# P15_ETH3_USB__USB_2_0_HUB.net
KiCad netlist of a schematic drawn in Altium Designer
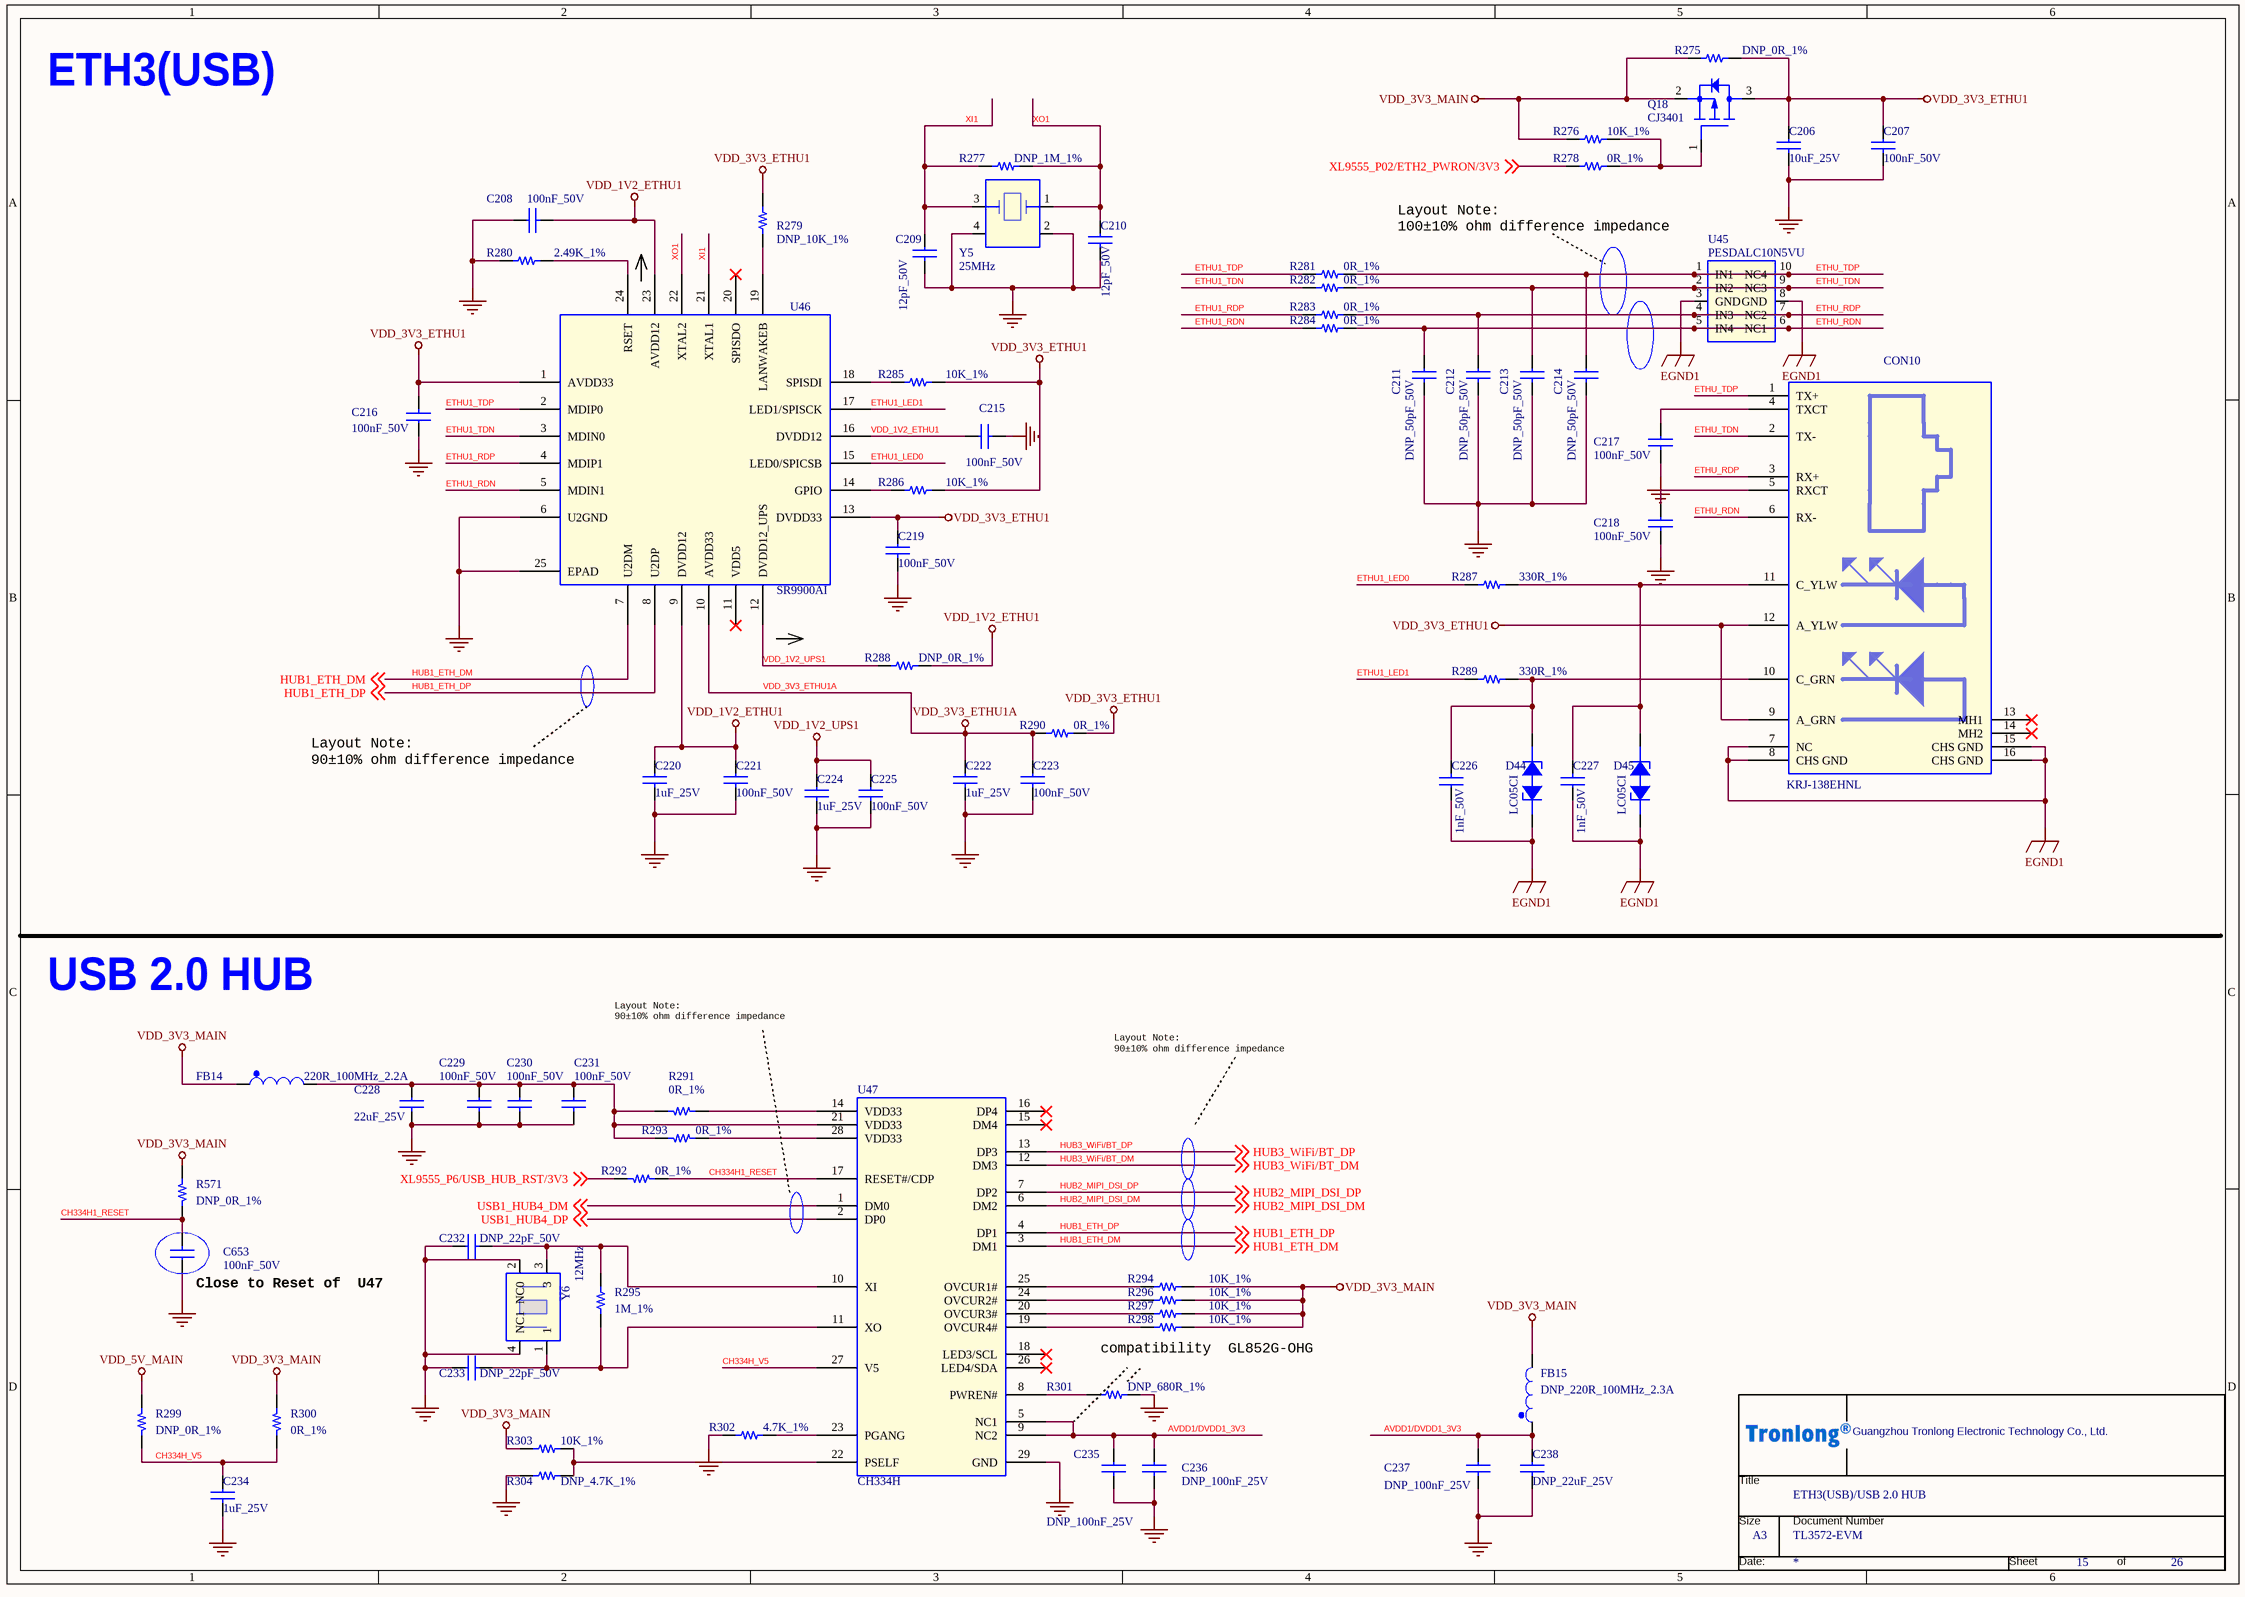
[diagram p0: P15_ETH3(USB)_USB 2.0 HUB.SchDoc]

(export (version "E")
  (design (tool "Eeschema 10.0.6"))
  (components
    (comp (ref "*")
      (value "Tronlong_TITTLE_20211115")
      (fields
        (field (name "DOC") "TL3572-EVM")
        (field (name "TITLE") "ETH3(USB)/USB 2.0 HUB")
        (field (name "ORGNAME") "Guangzhou Tronlong Electronic Technology Co., Ltd.")
        (field (name "PAGE SIZE") "A3")
        (field (name "PAGE NUMBER") "15")
        (field (name "PAGE COUNT") "26")
      )
      (libsource (lib "*") (part "Tronlong_TITTLE_20211115"))
    )
    (comp (ref "C206")
      (value "10uF_25V")
      (footprint "C0603")
      (description "贴片陶瓷电容,10uF,20%,25V,X5R")
      (fields
        (field (name "MANUFACTURER") "广东风华高新科技股份有限公司（FH）")
        (field (name "MANUFACTURER PARTNUMBER") "0603X106M250NT")
      )
      (libsource (lib "*") (part "CAP NP_Dup2"))
    )
    (comp (ref "C207")
      (value "100nF_50V")
      (footprint "C0402")
      (description "贴片陶瓷电容,100nF,10%,50V,X7R")
      (fields
        (field (name "MANUFACTURER") "广东风华高新科技股份有限公司（FH）")
        (field (name "MANUFACTURER PARTNUMBER") "0402B104K500NT")
      )
      (libsource (lib "*") (part "CAP NP_Dup2"))
    )
    (comp (ref "C208")
      (value "100nF_50V")
      (footprint "C0402")
      (description "贴片陶瓷电容,100nF,10%,50V,X7R")
      (fields
        (field (name "MANUFACTURER") "广东风华高新科技股份有限公司（FH）")
        (field (name "MANUFACTURER PARTNUMBER") "0402B104K500NT")
      )
      (libsource (lib "*") (part "CAP NP_Dup2"))
    )
    (comp (ref "C209")
      (value "12pF_50V")
      (footprint "C0402")
      (description "贴片陶瓷电容,12pF,5%,50V,COG")
      (fields
        (field (name "MANUFACTURER") "广东风华高新科技股份有限公司（FH）")
        (field (name "MANUFACTURER PARTNUMBER") "0402CG120J500NT")
      )
      (libsource (lib "*") (part "CAP NP_Dup2"))
    )
    (comp (ref "C210")
      (value "12pF_50V")
      (footprint "C0402")
      (description "贴片陶瓷电容,12pF,5%,50V,COG")
      (fields
        (field (name "MANUFACTURER PARTNUMBER") "0402CG120J500NT")
        (field (name "MANUFACTURER") "广东风华高新科技股份有限公司（FH）")
      )
      (libsource (lib "*") (part "CAP NP_Dup2"))
    )
    (comp (ref "C211")
      (value "DNP_50pF_50V")
      (footprint "C0402")
      (description "贴片陶瓷电容,100nF,10%,50V,X7R")
      (fields
        (field (name "MANUFACTURER") "广东风华高新科技股份有限公司（FH）")
        (field (name "MANUFACTURER PARTNUMBER") "0402B104K500NT")
      )
      (libsource (lib "*") (part "CAP NP_Dup2"))
    )
    (comp (ref "C212")
      (value "DNP_50pF_50V")
      (footprint "C0402")
      (description "贴片陶瓷电容,100nF,10%,50V,X7R")
      (fields
        (field (name "MANUFACTURER") "广东风华高新科技股份有限公司（FH）")
        (field (name "MANUFACTURER PARTNUMBER") "0402B104K500NT")
      )
      (libsource (lib "*") (part "CAP NP_Dup2"))
    )
    (comp (ref "C213")
      (value "DNP_50pF_50V")
      (footprint "C0402")
      (description "贴片陶瓷电容,100nF,10%,50V,X7R")
      (fields
        (field (name "MANUFACTURER") "广东风华高新科技股份有限公司（FH）")
        (field (name "MANUFACTURER PARTNUMBER") "0402B104K500NT")
      )
      (libsource (lib "*") (part "CAP NP_Dup2"))
    )
    (comp (ref "C214")
      (value "DNP_50pF_50V")
      (footprint "C0402")
      (description "贴片陶瓷电容,100nF,10%,50V,X7R")
      (fields
        (field (name "MANUFACTURER") "广东风华高新科技股份有限公司（FH）")
        (field (name "MANUFACTURER PARTNUMBER") "0402B104K500NT")
      )
      (libsource (lib "*") (part "CAP NP_Dup2"))
    )
    (comp (ref "C215")
      (value "100nF_50V")
      (footprint "C0402")
      (description "贴片陶瓷电容,100nF,10%,50V,X7R")
      (fields
        (field (name "MANUFACTURER PARTNUMBER") "0402B104K500NT")
        (field (name "MANUFACTURER") "广东风华高新科技股份有限公司（FH）")
      )
      (libsource (lib "*") (part "CAP NP_Dup2"))
    )
    (comp (ref "C216")
      (value "100nF_50V")
      (footprint "C0402")
      (description "贴片陶瓷电容,100nF,10%,50V,X7R")
      (fields
        (field (name "MANUFACTURER") "广东风华高新科技股份有限公司（FH）")
        (field (name "MANUFACTURER PARTNUMBER") "0402B104K500NT")
      )
      (libsource (lib "*") (part "CAP NP_Dup2"))
    )
    (comp (ref "C217")
      (value "100nF_50V")
      (footprint "C0402")
      (description "贴片陶瓷电容,100nF,10%,50V,X7R")
      (fields
        (field (name "MANUFACTURER") "广东风华高新科技股份有限公司（FH）")
        (field (name "MANUFACTURER PARTNUMBER") "0402B104K500NT")
      )
      (libsource (lib "*") (part "CAP NP_Dup2"))
    )
    (comp (ref "C218")
      (value "100nF_50V")
      (footprint "C0402")
      (description "贴片陶瓷电容,100nF,10%,50V,X7R")
      (fields
        (field (name "MANUFACTURER PARTNUMBER") "0402B104K500NT")
        (field (name "MANUFACTURER") "广东风华高新科技股份有限公司（FH）")
      )
      (libsource (lib "*") (part "CAP NP_Dup2"))
    )
    (comp (ref "C219")
      (value "100nF_50V")
      (footprint "C0402")
      (description "贴片陶瓷电容,100nF,10%,50V,X7R")
      (fields
        (field (name "MANUFACTURER") "广东风华高新科技股份有限公司（FH）")
        (field (name "MANUFACTURER PARTNUMBER") "0402B104K500NT")
      )
      (libsource (lib "*") (part "CAP NP_Dup2"))
    )
    (comp (ref "C220")
      (value "1uF_25V")
      (footprint "C0402")
      (description "贴片陶瓷电容,1uF,10%,25V,X5R")
      (fields
        (field (name "MANUFACTURER") "广东风华高新科技股份有限公司（FH）")
        (field (name "MANUFACTURER PARTNUMBER") "0402X105K250NT")
      )
      (libsource (lib "*") (part "CAP NP_Dup2"))
    )
    (comp (ref "C221")
      (value "100nF_50V")
      (footprint "C0402")
      (description "贴片陶瓷电容,100nF,10%,50V,X7R")
      (fields
        (field (name "MANUFACTURER PARTNUMBER") "0402B104K500NT")
        (field (name "MANUFACTURER") "广东风华高新科技股份有限公司（FH）")
      )
      (libsource (lib "*") (part "CAP NP_Dup2"))
    )
    (comp (ref "C222")
      (value "1uF_25V")
      (footprint "C0402")
      (description "贴片陶瓷电容,1uF,10%,25V,X5R")
      (fields
        (field (name "MANUFACTURER") "广东风华高新科技股份有限公司（FH）")
        (field (name "MANUFACTURER PARTNUMBER") "0402X105K250NT")
      )
      (libsource (lib "*") (part "CAP NP_Dup2"))
    )
    (comp (ref "C223")
      (value "100nF_50V")
      (footprint "C0402")
      (description "贴片陶瓷电容,100nF,10%,50V,X7R")
      (fields
        (field (name "MANUFACTURER") "广东风华高新科技股份有限公司（FH）")
        (field (name "MANUFACTURER PARTNUMBER") "0402B104K500NT")
      )
      (libsource (lib "*") (part "CAP NP_Dup2"))
    )
    (comp (ref "C224")
      (value "1uF_25V")
      (footprint "C0402")
      (description "贴片陶瓷电容,1uF,10%,25V,X5R")
      (fields
        (field (name "MANUFACTURER") "广东风华高新科技股份有限公司（FH）")
        (field (name "MANUFACTURER PARTNUMBER") "0402X105K250NT")
      )
      (libsource (lib "*") (part "CAP NP_Dup2"))
    )
    (comp (ref "C225")
      (value "100nF_50V")
      (footprint "C0402")
      (description "贴片陶瓷电容,100nF,10%,50V,X7R")
      (fields
        (field (name "MANUFACTURER PARTNUMBER") "0402B104K500NT")
        (field (name "MANUFACTURER") "广东风华高新科技股份有限公司（FH）")
      )
      (libsource (lib "*") (part "CAP NP_Dup2"))
    )
    (comp (ref "C226")
      (value "1nF_50V")
      (footprint "C0402")
      (description "贴片陶瓷电容,1nF,10%,50V,X7R")
      (fields
        (field (name "TOLERANCE") "±10%")
        (field (name "MANUFACTURER") "广东风华高新科技股份有限公司（FH）")
        (field (name "CREATED BY") "JJJ")
      )
      (libsource (lib "*") (part "CAP NP_1"))
    )
    (comp (ref "C227")
      (value "1nF_50V")
      (footprint "C0402")
      (description "贴片陶瓷电容,1nF,10%,50V,X7R")
      (fields
        (field (name "MANUFACTURER PARTNUMBER") "0402B102K500NT")
        (field (name "MANUFACTURER") "广东风华高新科技股份有限公司（FH）")
        (field (name "CREATED BY") "JJJ")
      )
      (libsource (lib "*") (part "CAP NP_1"))
    )
    (comp (ref "C228")
      (value "22uF_25V")
      (footprint "C0805")
      (description "贴片陶瓷电容,22uF,20%,25V,X5R")
      (fields
        (field (name "MANUFACTURER PARTNUMBER") "0805X226M250NT")
        (field (name "MANUFACTURER") "广东风华高新科技股份有限公司（FH）")
      )
      (libsource (lib "*") (part "CAP NP_Dup2"))
    )
    (comp (ref "C229")
      (value "100nF_50V")
      (footprint "C0402")
      (description "贴片陶瓷电容,100nF,10%,50V,X7R")
      (fields
        (field (name "MANUFACTURER PARTNUMBER") "0402B104K500NT")
        (field (name "MANUFACTURER") "广东风华高新科技股份有限公司（FH）")
      )
      (libsource (lib "*") (part "CAP NP_Dup2"))
    )
    (comp (ref "C230")
      (value "100nF_50V")
      (footprint "C0402")
      (description "贴片陶瓷电容,100nF,10%,50V,X7R")
      (fields
        (field (name "MANUFACTURER PARTNUMBER") "0402B104K500NT")
        (field (name "MANUFACTURER") "广东风华高新科技股份有限公司（FH）")
      )
      (libsource (lib "*") (part "CAP NP_Dup2"))
    )
    (comp (ref "C231")
      (value "100nF_50V")
      (footprint "C0402")
      (description "贴片陶瓷电容,100nF,10%,50V,X7R")
      (fields
        (field (name "MANUFACTURER PARTNUMBER") "0402B104K500NT")
        (field (name "MANUFACTURER") "广东风华高新科技股份有限公司（FH）")
      )
      (libsource (lib "*") (part "CAP NP_Dup2"))
    )
    (comp (ref "C232")
      (value "DNP_22pF_50V")
      (footprint "C0603")
      (description "贴片陶瓷电容,22pF,5%,50V,COG")
      (fields
        (field (name "MANUFACTURER PARTNUMBER") "0603CG220J500NT")
        (field (name "MANUFACTURER") "广东风华高新科技股份有限公司（FH）")
      )
      (libsource (lib "*") (part "CAP NP_Dup2"))
    )
    (comp (ref "C233")
      (value "DNP_22pF_50V")
      (footprint "C0603")
      (description "贴片陶瓷电容,22pF,5%,50V,COG")
      (fields
        (field (name "MANUFACTURER") "广东风华高新科技股份有限公司（FH）")
        (field (name "MANUFACTURER PARTNUMBER") "0603CG220J500NT")
      )
      (libsource (lib "*") (part "CAP NP_Dup2"))
    )
    (comp (ref "C234")
      (value "1uF_25V")
      (footprint "C0402")
      (description "贴片陶瓷电容,1uF,10%,25V,X5R")
      (fields
        (field (name "MANUFACTURER") "广东风华高新科技股份有限公司（FH）")
        (field (name "MANUFACTURER PARTNUMBER") "0402X105K250NT")
      )
      (libsource (lib "*") (part "CAP NP_Dup2"))
    )
    (comp (ref "C235")
      (value "DNP_100nF_25V")
      (footprint "C0402")
      (description "贴片陶瓷电容,100nF,10%,25V,X7R")
      (fields
        (field (name "MANUFACTURER PARTNUMBER") "0402B104K250NT")
        (field (name "MANUFACTURER") "广东风华高新科技股份有限公司（FH）")
      )
      (libsource (lib "*") (part "CAP NP_Dup2"))
    )
    (comp (ref "C236")
      (value "DNP_100nF_25V")
      (footprint "C0402")
      (description "贴片陶瓷电容,100nF,10%,25V,X7R")
      (fields
        (field (name "MANUFACTURER PARTNUMBER") "0402B104K250NT")
        (field (name "MANUFACTURER") "广东风华高新科技股份有限公司（FH）")
      )
      (libsource (lib "*") (part "CAP NP_Dup2"))
    )
    (comp (ref "C237")
      (value "DNP_100nF_25V")
      (footprint "C0402")
      (description "贴片陶瓷电容,100nF,10%,25V,X7R")
      (fields
        (field (name "MANUFACTURER") "广东风华高新科技股份有限公司（FH）")
        (field (name "MANUFACTURER PARTNUMBER") "0402B104K250NT")
      )
      (libsource (lib "*") (part "CAP NP_Dup2"))
    )
    (comp (ref "C238")
      (value "DNP_22uF_25V")
      (footprint "C0805")
      (description "CL21A226MAQNNNE，CL21A226MAYNNNE")
      (fields
        (field (name "MANUFACTURER PARTNUMBER") "22uF,20%,C0805,25V,（X7R,X5R,COG,NPO或X7S）")
        (field (name "MANUFACTURER") "广州创龙")
      )
      (libsource (lib "*") (part "CAP NP_Dup2"))
    )
    (comp (ref "C653")
      (value "100nF_50V")
      (footprint "C0402")
      (description "贴片陶瓷电容,100nF,10%,50V,X7R")
      (fields
        (field (name "MANUFACTURER") "广东风华高新科技股份有限公司（FH）")
        (field (name "MANUFACTURER PARTNUMBER") "0402B104K500NT")
      )
      (libsource (lib "*") (part "CAP NP_Dup2"))
    )
    (comp (ref "CON10")
      (value "KRJ-138EHNL")
      (footprint "CON_YDS_13F-64GYD2PLXNL")
      (description "RJ45连接器,12P,2.54mm间距,单层母座,90度,插件")
      (fields (field (name "MANUFACTURER") "东莞市科优达电子科技有限公司（DGKYD）"))
      (libsource (lib "*") (part "ETHERNET CONNECTER"))
    )
    (comp (ref "D44")
      (value "LC05CI")
      (footprint "SOD323")
      (description "TVS二极管,VRWM=5V,VBR=6V,一组,双向,30KV,30KV")
      (fields
        (field (name "MANUFACTURER") "上海雷卯电子科技有限公司（Leiditech）")
        (field (name "MANUFACTURER PART NUMBER") "PESD3V3L1BA")
      )
      (libsource (lib "*") (part "DIODE BREAKDOWN_2"))
    )
    (comp (ref "D45")
      (value "LC05CI")
      (footprint "SOD323")
      (description "TVS二极管,VRWM=5V,VBR=6V,一组,双向,30KV,30KV")
      (fields
        (field (name "MANUFACTURER") "上海雷卯电子科技有限公司（Leiditech）")
        (field (name "MANUFACTURER PART NUMBER") "PESD3V3L1BA")
      )
      (libsource (lib "*") (part "DIODE BREAKDOWN_2"))
    )
    (comp (ref "FB14")
      (value "220R_100MHz_2.2A")
      (footprint "L0603")
      (description "磁珠,50mΩ,2.2A,220R@100MHz")
      (fields
        (field (name "MANUFACTURER PARTNUMBER") "UPZ1608U221-2R2TF")
        (field (name "MANUFACTURER") "深圳顺络电子股份有限公司（Sunlord）")
      )
      (libsource (lib "*") (part "FERRITE BEAD"))
    )
    (comp (ref "FB15")
      (value "DNP_220R_100MHz_2.3A")
      (footprint "L0603")
      (description "磁珠,50mΩ,2.3A,220R@100MHz")
      (fields
        (field (name "MANUFACTURER PARTNUMBER") "UPZ1608U221-2R3TF")
        (field (name "MANUFACTURER") "深圳顺络电子股份有限公司（Sunlord）")
      )
      (libsource (lib "*") (part "FERRITE BEAD"))
    )
    (comp (ref "Q18")
      (value "CJ3401")
      (footprint "SOT23-3")
      (description "MOSFET,P沟道,VDSS=-30V,VGSS=±12V,ID=-4.2A,PD=0.35W,VGS(th)=-1.3V")
      (fields (field (name "MANUFACTURER") "江苏长晶科技股份有限公司（JSCJ）"))
      (libsource (lib "*") (part "MOSFET P SOT"))
    )
    (comp (ref "R275")
      (value "DNP_0R_1%")
      (footprint "R0603")
      (description "贴片电阻,0R,±1%,1/10W")
      (fields
        (field (name "MANUFACTURER PARTNUMBER") "RS-03000FT")
        (field (name "MANUFACTURER") "广东风华高新科技股份有限公司（FH）")
      )
      (libsource (lib "*") (part "Resistor_Dup3"))
    )
    (comp (ref "R276")
      (value "10K_1%")
      (footprint "R0402")
      (description "贴片电阻,10K,±1%,1/16W")
      (fields
        (field (name "MANUFACTURER") "广东风华高新科技股份有限公司（FH）")
        (field (name "MANUFACTURER PARTNUMBER") "RC-02K1002FT")
      )
      (libsource (lib "*") (part "Resistor_Dup3"))
    )
    (comp (ref "R277")
      (value "DNP_1M_1%")
      (footprint "R0603")
      (description "0603WAF1004T5E,RC0603FR-071ML")
      (fields
        (field (name "MANUFACTURER") "广州创龙")
        (field (name "MANUFACTURER PARTNUMBER") "1M,±1%,R0603,≥1/10W")
      )
      (libsource (lib "*") (part "Resistor_Dup3"))
    )
    (comp (ref "R278")
      (value "0R_1%")
      (footprint "R0402")
      (description "贴片电阻,0R,±1%,1/16W")
      (fields
        (field (name "MANUFACTURER PARTNUMBER") "RC-02000FT")
        (field (name "MANUFACTURER") "广东风华高新科技股份有限公司（FH）")
      )
      (libsource (lib "*") (part "Resistor_Dup3"))
    )
    (comp (ref "R279")
      (value "DNP_10K_1%")
      (footprint "R0402")
      (description "贴片电阻,10K,±1%,1/16W")
      (fields
        (field (name "MANUFACTURER PARTNUMBER") "RC-02K1002FT")
        (field (name "MANUFACTURER") "广东风华高新科技股份有限公司（FH）")
      )
      (libsource (lib "*") (part "Resistor_Dup3"))
    )
    (comp (ref "R280")
      (value "2.49K_1%")
      (footprint "R0603")
      (description "贴片电阻,2.49K,±1%,1/10W")
      (fields
        (field (name "MANUFACTURER PARTNUMBER") "RS-03K2491FT")
        (field (name "MANUFACTURER") "广东风华高新科技股份有限公司（FH）")
      )
      (libsource (lib "*") (part "Resistor_Dup3"))
    )
    (comp (ref "R281")
      (value "0R_1%")
      (footprint "R0402")
      (description "贴片电阻,0R,±1%,1/16W")
      (fields
        (field (name "MANUFACTURER") "广东风华高新科技股份有限公司（FH）")
        (field (name "MANUFACTURER PARTNUMBER") "RC-02000FT")
      )
      (libsource (lib "*") (part "Resistor_Dup3"))
    )
    (comp (ref "R282")
      (value "0R_1%")
      (footprint "R0402")
      (description "贴片电阻,0R,±1%,1/16W")
      (fields
        (field (name "MANUFACTURER") "广东风华高新科技股份有限公司（FH）")
        (field (name "MANUFACTURER PARTNUMBER") "RC-02000FT")
      )
      (libsource (lib "*") (part "Resistor_Dup3"))
    )
    (comp (ref "R283")
      (value "0R_1%")
      (footprint "R0402")
      (description "贴片电阻,0R,±1%,1/16W")
      (fields
        (field (name "MANUFACTURER") "广东风华高新科技股份有限公司（FH）")
        (field (name "MANUFACTURER PARTNUMBER") "RC-02000FT")
      )
      (libsource (lib "*") (part "Resistor_Dup3"))
    )
    (comp (ref "R284")
      (value "0R_1%")
      (footprint "R0402")
      (description "贴片电阻,0R,±1%,1/16W")
      (fields
        (field (name "MANUFACTURER") "广东风华高新科技股份有限公司（FH）")
        (field (name "MANUFACTURER PARTNUMBER") "RC-02000FT")
      )
      (libsource (lib "*") (part "Resistor_Dup3"))
    )
    (comp (ref "R285")
      (value "10K_1%")
      (footprint "R0402")
      (description "贴片电阻,10K,±1%,1/16W")
      (fields
        (field (name "MANUFACTURER") "广东风华高新科技股份有限公司（FH）")
        (field (name "MANUFACTURER PARTNUMBER") "RC-02K1002FT")
      )
      (libsource (lib "*") (part "Resistor_Dup3"))
    )
    (comp (ref "R286")
      (value "10K_1%")
      (footprint "R0402")
      (description "贴片电阻,10K,±1%,1/16W")
      (fields
        (field (name "MANUFACTURER PARTNUMBER") "RC-02K1002FT")
        (field (name "MANUFACTURER") "广东风华高新科技股份有限公司（FH）")
      )
      (libsource (lib "*") (part "Resistor_Dup3"))
    )
    (comp (ref "R287")
      (value "330R_1%")
      (footprint "R0402")
      (description "RC0402FR-07330RL,0402WGF3300TCE")
      (fields
        (field (name "MANUFACTURER PARTNUMBER") "330R,±1%,R0402,≥1/16W")
        (field (name "MANUFACTURER") "广州创龙")
      )
      (libsource (lib "*") (part "Resistor_Dup3"))
    )
    (comp (ref "R288")
      (value "DNP_0R_1%")
      (footprint "R0603")
      (description "贴片电阻,0R,±1%,1/10W")
      (fields
        (field (name "MANUFACTURER PARTNUMBER") "RS-03000FT")
        (field (name "MANUFACTURER") "广东风华高新科技股份有限公司（FH）")
      )
      (libsource (lib "*") (part "Resistor_Dup3"))
    )
    (comp (ref "R289")
      (value "330R_1%")
      (footprint "R0402")
      (description "RC0402FR-07330RL,0402WGF3300TCE")
      (fields
        (field (name "MANUFACTURER") "广州创龙")
        (field (name "MANUFACTURER PARTNUMBER") "330R,±1%,R0402,≥1/16W")
      )
      (libsource (lib "*") (part "Resistor_Dup3"))
    )
    (comp (ref "R290")
      (value "0R_1%")
      (footprint "R0603")
      (description "贴片电阻,0R,±1%,1/10W")
      (fields
        (field (name "MANUFACTURER") "广东风华高新科技股份有限公司（FH）")
        (field (name "MANUFACTURER PARTNUMBER") "RS-03000FT")
      )
      (libsource (lib "*") (part "Resistor_Dup3"))
    )
    (comp (ref "R291")
      (value "0R_1%")
      (footprint "R0402")
      (description "贴片电阻,0R,±1%,1/16W")
      (fields
        (field (name "MANUFACTURER") "广东风华高新科技股份有限公司（FH）")
        (field (name "MANUFACTURER PARTNUMBER") "RC-02000FT")
      )
      (libsource (lib "*") (part "Resistor_Dup3"))
    )
    (comp (ref "R292")
      (value "0R_1%")
      (footprint "R0402")
      (description "贴片电阻,0R,±1%,1/16W")
      (fields
        (field (name "MANUFACTURER") "广东风华高新科技股份有限公司（FH）")
        (field (name "MANUFACTURER PARTNUMBER") "RC-02000FT")
      )
      (libsource (lib "*") (part "Resistor_Dup3"))
    )
    (comp (ref "R293")
      (value "0R_1%")
      (footprint "R0402")
      (description "贴片电阻,0R,±1%,1/16W")
      (fields
        (field (name "MANUFACTURER") "广东风华高新科技股份有限公司（FH）")
        (field (name "MANUFACTURER PARTNUMBER") "RC-02000FT")
      )
      (libsource (lib "*") (part "Resistor_Dup3"))
    )
    (comp (ref "R294")
      (value "10K_1%")
      (footprint "R0402")
      (description "贴片电阻,10K,±1%,1/16W")
      (fields
        (field (name "MANUFACTURER") "广东风华高新科技股份有限公司（FH）")
        (field (name "MANUFACTURER PARTNUMBER") "RC-02K1002FT")
      )
      (libsource (lib "*") (part "Resistor_Dup3"))
    )
    (comp (ref "R295")
      (value "1M_1%")
      (footprint "R0402")
      (description "RC0402FR-071ML,0402WGF1004TCE")
      (fields
        (field (name "MANUFACTURER PARTNUMBER") "1M,±1%,R0402,≥1/16W")
        (field (name "MANUFACTURER") "广州创龙")
      )
      (libsource (lib "*") (part "Resistor_Dup3"))
    )
    (comp (ref "R296")
      (value "10K_1%")
      (footprint "R0402")
      (description "贴片电阻,10K,±1%,1/16W")
      (fields
        (field (name "MANUFACTURER") "广东风华高新科技股份有限公司（FH）")
        (field (name "MANUFACTURER PARTNUMBER") "RC-02K1002FT")
      )
      (libsource (lib "*") (part "Resistor_Dup3"))
    )
    (comp (ref "R297")
      (value "10K_1%")
      (footprint "R0402")
      (description "贴片电阻,10K,±1%,1/16W")
      (fields
        (field (name "MANUFACTURER PARTNUMBER") "RC-02K1002FT")
        (field (name "MANUFACTURER") "广东风华高新科技股份有限公司（FH）")
      )
      (libsource (lib "*") (part "Resistor_Dup3"))
    )
    (comp (ref "R298")
      (value "10K_1%")
      (footprint "R0402")
      (description "贴片电阻,10K,±1%,1/16W")
      (fields
        (field (name "MANUFACTURER") "广东风华高新科技股份有限公司（FH）")
        (field (name "MANUFACTURER PARTNUMBER") "RC-02K1002FT")
      )
      (libsource (lib "*") (part "Resistor_Dup3"))
    )
    (comp (ref "R299")
      (value "DNP_0R_1%")
      (footprint "R0402")
      (description "贴片电阻,0R,±1%,1/16W")
      (fields
        (field (name "MANUFACTURER") "广东风华高新科技股份有限公司（FH）")
        (field (name "MANUFACTURER PARTNUMBER") "RC-02000FT")
      )
      (libsource (lib "*") (part "Resistor_Dup3"))
    )
    (comp (ref "R300")
      (value "0R_1%")
      (footprint "R0603")
      (description "贴片电阻,0R,±1%,1/10W")
      (fields
        (field (name "MANUFACTURER PARTNUMBER") "RS-03000FT")
        (field (name "MANUFACTURER") "广东风华高新科技股份有限公司（FH）")
      )
      (libsource (lib "*") (part "Resistor_Dup3"))
    )
    (comp (ref "R301")
      (value "DNP_680R_1%")
      (footprint "R0603")
      (description "贴片电阻,680R,±1%,1/10W")
      (fields
        (field (name "MANUFACTURER") "广东风华高新科技股份有限公司（FH）")
        (field (name "MANUFACTURER PARTNUMBER") "RS-03K6800FT")
      )
      (libsource (lib "*") (part "Resistor_Dup3"))
    )
    (comp (ref "R302")
      (value "4.7K_1%")
      (footprint "R0402")
      (description "贴片电阻,4.7K,±1%,1/16W")
      (fields
        (field (name "MANUFACTURER PARTNUMBER") "RC-02K4701FT")
        (field (name "MANUFACTURER") "广东风华高新科技股份有限公司（FH）")
      )
      (libsource (lib "*") (part "Resistor_Dup3"))
    )
    (comp (ref "R303")
      (value "10K_1%")
      (footprint "R0402")
      (description "贴片电阻,10K,±1%,1/16W")
      (fields
        (field (name "MANUFACTURER") "广东风华高新科技股份有限公司（FH）")
        (field (name "MANUFACTURER PARTNUMBER") "RC-02K1002FT")
      )
      (libsource (lib "*") (part "Resistor_Dup3"))
    )
    (comp (ref "R304")
      (value "DNP_4.7K_1%")
      (footprint "R0402")
      (description "RC0402FR-074K7L,0402WGF4701TCE")
      (fields
        (field (name "MANUFACTURER") "广州创龙")
        (field (name "MANUFACTURER PARTNUMBER") "4.7K,±1%,R0402,≥1/16W")
      )
      (libsource (lib "*") (part "Resistor_Dup3"))
    )
    (comp (ref "R571")
      (value "DNP_0R_1%")
      (footprint "R0402")
      (description "贴片电阻,0R,±1%,1/16W")
      (fields
        (field (name "MANUFACTURER PARTNUMBER") "RC-02000FT")
        (field (name "MANUFACTURER") "广东风华高新科技股份有限公司（FH）")
      )
      (libsource (lib "*") (part "Resistor_Dup3"))
    )
    (comp (ref "U45")
      (value "PESDALC10N5VU")
      (footprint "DFN-10-2510")
      (description "ESD二极管,VRWM=5V,VBR=6V,四组,单向,15KV,30KV")
      (fields (field (name "MANUFACTURER") "上海芯导电子科技股份有限公司（Prisemi）"))
      (libsource (lib "*") (part "SU099PGTR"))
    )
    (comp (ref "U46")
      (value "SR9900AI")
      (footprint "QFN24-4X4-0d5")
      (description "以太网控制器，USB")
      (fields (field (name "MANUFACTURER") "深圳市和芯润德科技有限公司（CoreChips）"))
      (libsource (lib "*") (part "SR9900_1"))
    )
    (comp (ref "U47")
      (value "CH334H")
      (footprint "QFN28_5x5")
      (description "USB HUB控制器")
      (fields (field (name "MANUFACTURER") "南京沁恒微电子股份有限公司（WCH）"))
      (libsource (lib "*") (part "GL852GT_1"))
    )
    (comp (ref "Y5")
      (value "25MHz")
      (footprint "SMD_3225")
      (description "四脚无源晶振,25MHz,±10ppm,12pF,30Ω,±30ppm")
      (fields
        (field (name "MANUFACTURER PARTNUMBER") "S3B25.000F1210F30")
        (field (name "MANUFACTURER") "深圳市星通时频电子有限公司（SCTF）")
      )
      (libsource (lib "*") (part "CRYSTAL SMD 4PIN"))
    )
    (comp (ref "Y6")
      (value "12MHz")
      (footprint "SMD_3225")
      (description "四脚无源晶振,12MHz,±10ppm,12pF,100Ω,±30ppm")
      (fields
        (field (name "MANUFACTURER PARTNUMBER") "S3B12.000F1210F30")
        (field (name "MANUFACTURER") "深圳市星通时频电子有限公司（SCTF）")
      )
      (libsource (lib "*") (part "CRYSTAL"))
    )
  )
  (nets
    (net (code "1") (name "/AVDD1{slash}DVDD1_3V3") (class "Default")
      (node (ref "C235") (pin "1") (pinfunction "1_1") (pintype "passive"))
      (node (ref "C236") (pin "1") (pinfunction "1_1") (pintype "passive"))
      (node (ref "C237") (pin "1") (pinfunction "1_1") (pintype "passive"))
      (node (ref "C238") (pin "1") (pinfunction "1_1") (pintype "passive"))
      (node (ref "FB15") (pin "1") (pinfunction "1_1") (pintype "passive"))
      (node (ref "U47") (pin "5") (pinfunction "NC1_5") (pintype "passive"))
      (node (ref "U47") (pin "9") (pinfunction "NC2_9") (pintype "passive"))
    )
    (net (code "2") (name "/CH334H1_RESET") (class "Default")
      (node (ref "C653") (pin "2") (pinfunction "2_2") (pintype "passive"))
      (node (ref "R292") (pin "1") (pinfunction "1_1") (pintype "passive"))
      (node (ref "R571") (pin "1") (pinfunction "1_1") (pintype "passive"))
      (node (ref "U47") (pin "17") (pinfunction "RESET#/CDP_17") (pintype "passive"))
    )
    (net (code "3") (name "/CH334H_V5") (class "Default")
      (node (ref "C234") (pin "1") (pinfunction "1_1") (pintype "passive"))
      (node (ref "R299") (pin "1") (pinfunction "1_1") (pintype "passive"))
      (node (ref "R300") (pin "1") (pinfunction "1_1") (pintype "passive"))
      (node (ref "U47") (pin "27") (pinfunction "V5_27") (pintype "passive"))
    )
    (net (code "4") (name "/ETHU1_LED0") (class "Default")
      (node (ref "R287") (pin "1") (pinfunction "1_1") (pintype "passive"))
      (node (ref "U46") (pin "15") (pinfunction "LED0/SPICSB_15") (pintype "passive"))
    )
    (net (code "5") (name "/ETHU1_LED1") (class "Default")
      (node (ref "R289") (pin "1") (pinfunction "1_1") (pintype "passive"))
      (node (ref "U46") (pin "17") (pinfunction "LED1/SPISCK_17") (pintype "passive"))
    )
    (net (code "6") (name "/ETHU1_RDN") (class "Default")
      (node (ref "R284") (pin "2") (pinfunction "2_2") (pintype "passive"))
      (node (ref "U46") (pin "5") (pinfunction "MDIN1_5") (pintype "passive"))
    )
    (net (code "7") (name "/ETHU1_RDP") (class "Default")
      (node (ref "R283") (pin "2") (pinfunction "2_2") (pintype "passive"))
      (node (ref "U46") (pin "4") (pinfunction "MDIP1_4") (pintype "passive"))
    )
    (net (code "8") (name "/ETHU1_TDN") (class "Default")
      (node (ref "R282") (pin "2") (pinfunction "2_2") (pintype "passive"))
      (node (ref "U46") (pin "3") (pinfunction "MDIN0_3") (pintype "passive"))
    )
    (net (code "9") (name "/ETHU1_TDP") (class "Default")
      (node (ref "R281") (pin "2") (pinfunction "2_2") (pintype "passive"))
      (node (ref "U46") (pin "2") (pinfunction "MDIP0_2") (pintype "passive"))
    )
    (net (code "10") (name "/ETHU_RDN") (class "Default")
      (node (ref "C211") (pin "1") (pinfunction "1_1") (pintype "passive"))
      (node (ref "CON10") (pin "6") (pinfunction "RX-_6") (pintype "passive"))
      (node (ref "R284") (pin "1") (pinfunction "1_1") (pintype "passive"))
      (node (ref "U45") (pin "5") (pinfunction "IN4_5") (pintype "passive"))
      (node (ref "U45") (pin "6") (pinfunction "NC1_6") (pintype "passive"))
    )
    (net (code "11") (name "/ETHU_RDP") (class "Default")
      (node (ref "C212") (pin "1") (pinfunction "1_1") (pintype "passive"))
      (node (ref "CON10") (pin "3") (pinfunction "RX+_3") (pintype "passive"))
      (node (ref "R283") (pin "1") (pinfunction "1_1") (pintype "passive"))
      (node (ref "U45") (pin "4") (pinfunction "IN3_4") (pintype "passive"))
      (node (ref "U45") (pin "7") (pinfunction "NC2_7") (pintype "passive"))
    )
    (net (code "12") (name "/ETHU_TDN") (class "Default")
      (node (ref "C213") (pin "1") (pinfunction "1_1") (pintype "passive"))
      (node (ref "CON10") (pin "2") (pinfunction "TX-_2") (pintype "passive"))
      (node (ref "R282") (pin "1") (pinfunction "1_1") (pintype "passive"))
      (node (ref "U45") (pin "2") (pinfunction "IN2_2") (pintype "passive"))
      (node (ref "U45") (pin "9") (pinfunction "NC3_9") (pintype "passive"))
    )
    (net (code "13") (name "/ETHU_TDP") (class "Default")
      (node (ref "C214") (pin "1") (pinfunction "1_1") (pintype "passive"))
      (node (ref "CON10") (pin "1") (pinfunction "TX+_1") (pintype "passive"))
      (node (ref "R281") (pin "1") (pinfunction "1_1") (pintype "passive"))
      (node (ref "U45") (pin "1") (pinfunction "IN1_1") (pintype "passive"))
      (node (ref "U45") (pin "10") (pinfunction "NC4_10") (pintype "passive"))
    )
    (net (code "14") (name "/XI1") (class "Default")
      (node (ref "C209") (pin "1") (pinfunction "1_1") (pintype "passive"))
      (node (ref "R277") (pin "2") (pinfunction "2_2") (pintype "passive"))
      (node (ref "U46") (pin "21") (pinfunction "XTAL1_21") (pintype "passive"))
      (node (ref "Y5") (pin "3") (pinfunction "3_3") (pintype "passive"))
    )
    (net (code "15") (name "/XO1") (class "Default")
      (node (ref "C210") (pin "1") (pinfunction "1_1") (pintype "passive"))
      (node (ref "R277") (pin "1") (pinfunction "1_1") (pintype "passive"))
      (node (ref "U46") (pin "22") (pinfunction "XTAL2_22") (pintype "passive"))
      (node (ref "Y5") (pin "1") (pinfunction "1_1") (pintype "passive"))
    )
    (net (code "16") (name "EGND1") (class "Default")
      (node (ref "C226") (pin "1") (pinfunction "1_1") (pintype "passive"))
      (node (ref "C227") (pin "1") (pinfunction "1_1") (pintype "passive"))
      (node (ref "CON10") (pin "15") (pinfunction "CHS_GND_15") (pintype "power_in"))
      (node (ref "CON10") (pin "16") (pinfunction "CHS_GND_16") (pintype "power_in"))
      (node (ref "CON10") (pin "7") (pinfunction "NC_7") (pintype "passive"))
      (node (ref "CON10") (pin "8") (pinfunction "CHS_GND_8") (pintype "power_in"))
      (node (ref "D44") (pin "1") (pinfunction "ANODE1_1") (pintype "passive"))
      (node (ref "D45") (pin "1") (pinfunction "ANODE1_1") (pintype "passive"))
      (node (ref "U45") (pin "3") (pinfunction "GND_3") (pintype "power_in"))
      (node (ref "U45") (pin "8") (pinfunction "GND_8") (pintype "power_in"))
    )
    (net (code "17") (name "GND") (class "Default")
      (node (ref "C206") (pin "2") (pinfunction "2_2") (pintype "passive"))
      (node (ref "C207") (pin "2") (pinfunction "2_2") (pintype "passive"))
      (node (ref "C208") (pin "1") (pinfunction "1_1") (pintype "passive"))
      (node (ref "C209") (pin "2") (pinfunction "2_2") (pintype "passive"))
      (node (ref "C210") (pin "2") (pinfunction "2_2") (pintype "passive"))
      (node (ref "C211") (pin "2") (pinfunction "2_2") (pintype "passive"))
      (node (ref "C212") (pin "2") (pinfunction "2_2") (pintype "passive"))
      (node (ref "C213") (pin "2") (pinfunction "2_2") (pintype "passive"))
      (node (ref "C214") (pin "2") (pinfunction "2_2") (pintype "passive"))
      (node (ref "C215") (pin "2") (pinfunction "2_2") (pintype "passive"))
      (node (ref "C216") (pin "1") (pinfunction "1_1") (pintype "passive"))
      (node (ref "C217") (pin "2") (pinfunction "2_2") (pintype "passive"))
      (node (ref "C218") (pin "2") (pinfunction "2_2") (pintype "passive"))
      (node (ref "C219") (pin "2") (pinfunction "2_2") (pintype "passive"))
      (node (ref "C220") (pin "2") (pinfunction "2_2") (pintype "passive"))
      (node (ref "C221") (pin "2") (pinfunction "2_2") (pintype "passive"))
      (node (ref "C222") (pin "2") (pinfunction "2_2") (pintype "passive"))
      (node (ref "C223") (pin "2") (pinfunction "2_2") (pintype "passive"))
      (node (ref "C224") (pin "2") (pinfunction "2_2") (pintype "passive"))
      (node (ref "C225") (pin "2") (pinfunction "2_2") (pintype "passive"))
      (node (ref "C228") (pin "2") (pinfunction "2_2") (pintype "passive"))
      (node (ref "C229") (pin "2") (pinfunction "2_2") (pintype "passive"))
      (node (ref "C230") (pin "2") (pinfunction "2_2") (pintype "passive"))
      (node (ref "C231") (pin "2") (pinfunction "2_2") (pintype "passive"))
      (node (ref "C232") (pin "1") (pinfunction "1_1") (pintype "passive"))
      (node (ref "C233") (pin "1") (pinfunction "1_1") (pintype "passive"))
      (node (ref "C234") (pin "2") (pinfunction "2_2") (pintype "passive"))
      (node (ref "C235") (pin "2") (pinfunction "2_2") (pintype "passive"))
      (node (ref "C236") (pin "2") (pinfunction "2_2") (pintype "passive"))
      (node (ref "C237") (pin "2") (pinfunction "2_2") (pintype "passive"))
      (node (ref "C238") (pin "2") (pinfunction "2_2") (pintype "passive"))
      (node (ref "C653") (pin "1") (pinfunction "1_1") (pintype "passive"))
      (node (ref "R280") (pin "1") (pinfunction "1_1") (pintype "passive"))
      (node (ref "R301") (pin "2") (pinfunction "2_2") (pintype "passive"))
      (node (ref "R302") (pin "2") (pinfunction "2_2") (pintype "passive"))
      (node (ref "R304") (pin "2") (pinfunction "2_2") (pintype "passive"))
      (node (ref "U46") (pin "25") (pinfunction "EPAD_25") (pintype "power_in"))
      (node (ref "U46") (pin "6") (pinfunction "U2GND_6") (pintype "power_in"))
      (node (ref "U47") (pin "29") (pinfunction "GND_29") (pintype "power_in"))
      (node (ref "Y5") (pin "2") (pinfunction "2_2") (pintype "passive"))
      (node (ref "Y5") (pin "4") (pinfunction "4_4") (pintype "passive"))
      (node (ref "Y6") (pin "2") (pinfunction "NC0_2") (pintype "passive"))
      (node (ref "Y6") (pin "4") (pinfunction "NC1_4") (pintype "passive"))
    )
    (net (code "18") (name "HUB1_ETH_DM") (class "Default")
      (node (ref "U46") (pin "7") (pinfunction "U2DM_7") (pintype "passive"))
      (node (ref "U47") (pin "3") (pinfunction "DM1_3") (pintype "passive"))
    )
    (net (code "19") (name "HUB1_ETH_DP") (class "Default")
      (node (ref "U46") (pin "8") (pinfunction "U2DP_8") (pintype "passive"))
      (node (ref "U47") (pin "4") (pinfunction "DP1_4") (pintype "passive"))
    )
    (net (code "20") (name "HUB2_MIPI_DSI_DM") (class "Default")
      (node (ref "U47") (pin "6") (pinfunction "DM2_6") (pintype "passive"))
    )
    (net (code "21") (name "HUB2_MIPI_DSI_DP") (class "Default")
      (node (ref "U47") (pin "7") (pinfunction "DP2_7") (pintype "passive"))
    )
    (net (code "22") (name "HUB3_WiFi{slash}BT_DM") (class "Default")
      (node (ref "U47") (pin "12") (pinfunction "DM3_12") (pintype "passive"))
    )
    (net (code "23") (name "HUB3_WiFi{slash}BT_DP") (class "Default")
      (node (ref "U47") (pin "13") (pinfunction "DP3_13") (pintype "passive"))
    )
    (net (code "24") (name "Net-(C228-Pad1)") (class "Default")
      (node (ref "C228") (pin "1") (pinfunction "1_1") (pintype "passive"))
      (node (ref "C229") (pin "1") (pinfunction "1_1") (pintype "passive"))
      (node (ref "C230") (pin "1") (pinfunction "1_1") (pintype "passive"))
      (node (ref "C231") (pin "1") (pinfunction "1_1") (pintype "passive"))
      (node (ref "FB14") (pin "2") (pinfunction "2_2") (pintype "passive"))
      (node (ref "R291") (pin "1") (pinfunction "1_1") (pintype "passive"))
      (node (ref "R293") (pin "1") (pinfunction "1_1") (pintype "passive"))
      (node (ref "U47") (pin "21") (pinfunction "VDD33_21") (pintype "power_in"))
    )
    (net (code "25") (name "Net-(CON10-C_GRN)") (class "Default")
      (node (ref "C226") (pin "2") (pinfunction "2_2") (pintype "passive"))
      (node (ref "CON10") (pin "10") (pinfunction "C_GRN_10") (pintype "passive"))
      (node (ref "D44") (pin "2") (pinfunction "CATHODE2_2") (pintype "passive"))
      (node (ref "R289") (pin "2") (pinfunction "2_2") (pintype "passive"))
    )
    (net (code "26") (name "Net-(CON10-C_YLW)") (class "Default")
      (node (ref "C227") (pin "2") (pinfunction "2_2") (pintype "passive"))
      (node (ref "CON10") (pin "11") (pinfunction "C_YLW_11") (pintype "passive"))
      (node (ref "D45") (pin "2") (pinfunction "CATHODE2_2") (pintype "passive"))
      (node (ref "R287") (pin "2") (pinfunction "2_2") (pintype "passive"))
    )
    (net (code "27") (name "Net-(CON10-RXCT)") (class "Default")
      (node (ref "C218") (pin "1") (pinfunction "1_1") (pintype "passive"))
      (node (ref "CON10") (pin "5") (pinfunction "RXCT_5") (pintype "passive"))
    )
    (net (code "28") (name "Net-(CON10-TXCT)") (class "Default")
      (node (ref "C217") (pin "1") (pinfunction "1_1") (pintype "passive"))
      (node (ref "CON10") (pin "4") (pinfunction "TXCT_4") (pintype "passive"))
    )
    (net (code "29") (name "Net-(Q18-GATE)") (class "Default")
      (node (ref "Q18") (pin "1") (pinfunction "GATE_1") (pintype "passive"))
      (node (ref "R276") (pin "2") (pinfunction "2_2") (pintype "passive"))
      (node (ref "R278") (pin "1") (pinfunction "1_1") (pintype "passive"))
    )
    (net (code "30") (name "Net-(R291-Pad2)") (class "Default")
      (node (ref "R291") (pin "2") (pinfunction "2_2") (pintype "passive"))
      (node (ref "U47") (pin "14") (pinfunction "VDD33_14") (pintype "power_in"))
    )
    (net (code "31") (name "Net-(R293-Pad2)") (class "Default")
      (node (ref "R293") (pin "2") (pinfunction "2_2") (pintype "passive"))
      (node (ref "U47") (pin "28") (pinfunction "VDD33_28") (pintype "power_in"))
    )
    (net (code "32") (name "Net-(U46-GPIO)") (class "Default")
      (node (ref "R286") (pin "1") (pinfunction "1_1") (pintype "passive"))
      (node (ref "U46") (pin "14") (pinfunction "GPIO_14") (pintype "passive"))
    )
    (net (code "33") (name "Net-(U46-LANWAKEB)") (class "Default")
      (node (ref "R279") (pin "1") (pinfunction "1_1") (pintype "passive"))
      (node (ref "U46") (pin "19") (pinfunction "LANWAKEB_19") (pintype "passive"))
    )
    (net (code "34") (name "Net-(U46-RSET)") (class "Default")
      (node (ref "R280") (pin "2") (pinfunction "2_2") (pintype "passive"))
      (node (ref "U46") (pin "24") (pinfunction "RSET_24") (pintype "passive"))
    )
    (net (code "35") (name "Net-(U46-SPISDI)") (class "Default")
      (node (ref "R285") (pin "1") (pinfunction "1_1") (pintype "passive"))
      (node (ref "U46") (pin "18") (pinfunction "SPISDI_18") (pintype "passive"))
    )
    (net (code "36") (name "Net-(U47-OVCUR1#)") (class "Default")
      (node (ref "R294") (pin "1") (pinfunction "1_1") (pintype "passive"))
      (node (ref "U47") (pin "25") (pinfunction "OVCUR1#_25") (pintype "passive"))
    )
    (net (code "37") (name "Net-(U47-OVCUR2#)") (class "Default")
      (node (ref "R296") (pin "1") (pinfunction "1_1") (pintype "passive"))
      (node (ref "U47") (pin "24") (pinfunction "OVCUR2#_24") (pintype "passive"))
    )
    (net (code "38") (name "Net-(U47-OVCUR3#)") (class "Default")
      (node (ref "R297") (pin "1") (pinfunction "1_1") (pintype "passive"))
      (node (ref "U47") (pin "20") (pinfunction "OVCUR3#_20") (pintype "passive"))
    )
    (net (code "39") (name "Net-(U47-OVCUR4#)") (class "Default")
      (node (ref "R298") (pin "1") (pinfunction "1_1") (pintype "passive"))
      (node (ref "U47") (pin "19") (pinfunction "OVCUR4#_19") (pintype "passive"))
    )
    (net (code "40") (name "Net-(U47-PGANG)") (class "Default")
      (node (ref "R302") (pin "1") (pinfunction "1_1") (pintype "passive"))
      (node (ref "U47") (pin "23") (pinfunction "PGANG_23") (pintype "passive"))
    )
    (net (code "41") (name "Net-(U47-PSELF)") (class "Default")
      (node (ref "R303") (pin "2") (pinfunction "2_2") (pintype "passive"))
      (node (ref "R304") (pin "1") (pinfunction "1_1") (pintype "passive"))
      (node (ref "U47") (pin "22") (pinfunction "PSELF_22") (pintype "passive"))
    )
    (net (code "42") (name "Net-(U47-PWREN#)") (class "Default")
      (node (ref "R301") (pin "1") (pinfunction "1_1") (pintype "passive"))
      (node (ref "U47") (pin "8") (pinfunction "PWREN#_8") (pintype "passive"))
    )
    (net (code "43") (name "Net-(U47-XI)") (class "Default")
      (node (ref "C232") (pin "2") (pinfunction "2_2") (pintype "passive"))
      (node (ref "R295") (pin "1") (pinfunction "1_1") (pintype "passive"))
      (node (ref "U47") (pin "10") (pinfunction "XI_10") (pintype "passive"))
      (node (ref "Y6") (pin "3") (pinfunction "3_3") (pintype "passive"))
    )
    (net (code "44") (name "Net-(U47-XO)") (class "Default")
      (node (ref "C233") (pin "2") (pinfunction "2_2") (pintype "passive"))
      (node (ref "R295") (pin "2") (pinfunction "2_2") (pintype "passive"))
      (node (ref "U47") (pin "11") (pinfunction "XO_11") (pintype "passive"))
      (node (ref "Y6") (pin "1") (pinfunction "1_1") (pintype "passive"))
    )
    (net (code "45") (name "USB1_HUB4_DM") (class "Default")
      (node (ref "U47") (pin "1") (pinfunction "DM0_1") (pintype "passive"))
    )
    (net (code "46") (name "USB1_HUB4_DP") (class "Default")
      (node (ref "U47") (pin "2") (pinfunction "DP0_2") (pintype "passive"))
    )
    (net (code "47") (name "VDD_1V2_ETHU1") (class "Default")
      (node (ref "C208") (pin "2") (pinfunction "2_2") (pintype "passive"))
      (node (ref "C215") (pin "1") (pinfunction "1_1") (pintype "passive"))
      (node (ref "C220") (pin "1") (pinfunction "1_1") (pintype "passive"))
      (node (ref "C221") (pin "1") (pinfunction "1_1") (pintype "passive"))
      (node (ref "R288") (pin "2") (pinfunction "2_2") (pintype "passive"))
      (node (ref "U46") (pin "16") (pinfunction "DVDD12_16") (pintype "power_in"))
      (node (ref "U46") (pin "23") (pinfunction "AVDD12_23") (pintype "power_in"))
      (node (ref "U46") (pin "9") (pinfunction "DVDD12_9") (pintype "power_in"))
    )
    (net (code "48") (name "VDD_1V2_UPS1") (class "Default")
      (node (ref "C224") (pin "1") (pinfunction "1_1") (pintype "passive"))
      (node (ref "C225") (pin "1") (pinfunction "1_1") (pintype "passive"))
      (node (ref "R288") (pin "1") (pinfunction "1_1") (pintype "passive"))
      (node (ref "U46") (pin "12") (pinfunction "DVDD12_UPS_12") (pintype "power_in"))
    )
    (net (code "49") (name "VDD_3V3_ETHU1") (class "Default")
      (node (ref "C206") (pin "1") (pinfunction "1_1") (pintype "passive"))
      (node (ref "C207") (pin "1") (pinfunction "1_1") (pintype "passive"))
      (node (ref "C216") (pin "2") (pinfunction "2_2") (pintype "passive"))
      (node (ref "C219") (pin "1") (pinfunction "1_1") (pintype "passive"))
      (node (ref "CON10") (pin "12") (pinfunction "A_YLW_12") (pintype "passive"))
      (node (ref "CON10") (pin "9") (pinfunction "A_GRN_9") (pintype "passive"))
      (node (ref "Q18") (pin "3") (pinfunction "DRAIN_3") (pintype "passive"))
      (node (ref "R275") (pin "2") (pinfunction "2_2") (pintype "passive"))
      (node (ref "R279") (pin "2") (pinfunction "2_2") (pintype "passive"))
      (node (ref "R285") (pin "2") (pinfunction "2_2") (pintype "passive"))
      (node (ref "R286") (pin "2") (pinfunction "2_2") (pintype "passive"))
      (node (ref "R290") (pin "2") (pinfunction "2_2") (pintype "passive"))
      (node (ref "U46") (pin "1") (pinfunction "AVDD33_1") (pintype "power_in"))
      (node (ref "U46") (pin "13") (pinfunction "DVDD33_13") (pintype "power_in"))
    )
    (net (code "50") (name "VDD_3V3_ETHU1A") (class "Default")
      (node (ref "C222") (pin "1") (pinfunction "1_1") (pintype "passive"))
      (node (ref "C223") (pin "1") (pinfunction "1_1") (pintype "passive"))
      (node (ref "R290") (pin "1") (pinfunction "1_1") (pintype "passive"))
      (node (ref "U46") (pin "10") (pinfunction "AVDD33_10") (pintype "power_in"))
    )
    (net (code "51") (name "VDD_3V3_MAIN") (class "Default")
      (node (ref "FB14") (pin "1") (pinfunction "1_1") (pintype "passive"))
      (node (ref "FB15") (pin "2") (pinfunction "2_2") (pintype "passive"))
      (node (ref "Q18") (pin "2") (pinfunction "SOURCE_2") (pintype "passive"))
      (node (ref "R275") (pin "1") (pinfunction "1_1") (pintype "passive"))
      (node (ref "R276") (pin "1") (pinfunction "1_1") (pintype "passive"))
      (node (ref "R294") (pin "2") (pinfunction "2_2") (pintype "passive"))
      (node (ref "R296") (pin "2") (pinfunction "2_2") (pintype "passive"))
      (node (ref "R297") (pin "2") (pinfunction "2_2") (pintype "passive"))
      (node (ref "R298") (pin "2") (pinfunction "2_2") (pintype "passive"))
      (node (ref "R300") (pin "2") (pinfunction "2_2") (pintype "passive"))
      (node (ref "R303") (pin "1") (pinfunction "1_1") (pintype "passive"))
      (node (ref "R571") (pin "2") (pinfunction "2_2") (pintype "passive"))
    )
    (net (code "52") (name "VDD_5V_MAIN") (class "Default")
      (node (ref "R299") (pin "2") (pinfunction "2_2") (pintype "passive"))
    )
    (net (code "53") (name "XL9555_P02{slash}ETH2_PWRON{slash}3V3") (class "Default")
      (node (ref "R278") (pin "2") (pinfunction "2_2") (pintype "passive"))
    )
    (net (code "54") (name "XL9555_P6{slash}USB_HUB_RST{slash}3V3") (class "Default")
      (node (ref "R292") (pin "2") (pinfunction "2_2") (pintype "passive"))
    )
    (net (code "55") (name "unconnected-(CON10-MH1-Pad13)") (class "Default")
      (node (ref "CON10") (pin "13") (pinfunction "MH1_13") (pintype "passive+no_connect"))
    )
    (net (code "56") (name "unconnected-(CON10-MH2-Pad14)") (class "Default")
      (node (ref "CON10") (pin "14") (pinfunction "MH2_14") (pintype "passive+no_connect"))
    )
    (net (code "57") (name "unconnected-(U46-SPISDO-Pad20)") (class "Default")
      (node (ref "U46") (pin "20") (pinfunction "SPISDO_20") (pintype "passive+no_connect"))
    )
    (net (code "58") (name "unconnected-(U46-VDD5-Pad11)") (class "Default")
      (node (ref "U46") (pin "11") (pinfunction "VDD5_11") (pintype "passive+no_connect"))
    )
    (net (code "59") (name "unconnected-(U47-DM4-Pad15)") (class "Default")
      (node (ref "U47") (pin "15") (pinfunction "DM4_15") (pintype "passive+no_connect"))
    )
    (net (code "60") (name "unconnected-(U47-DP4-Pad16)") (class "Default")
      (node (ref "U47") (pin "16") (pinfunction "DP4_16") (pintype "passive+no_connect"))
    )
    (net (code "61") (name "unconnected-(U47-LED3{slash}SCL-Pad18)") (class "Default")
      (node (ref "U47") (pin "18") (pinfunction "LED3/SCL_18") (pintype "passive+no_connect"))
    )
    (net (code "62") (name "unconnected-(U47-LED4{slash}SDA-Pad26)") (class "Default")
      (node (ref "U47") (pin "26") (pinfunction "LED4/SDA_26") (pintype "passive+no_connect"))
    )
  )
)
